# CPU.net
KiCad netlist of a schematic drawn in Altium Designer
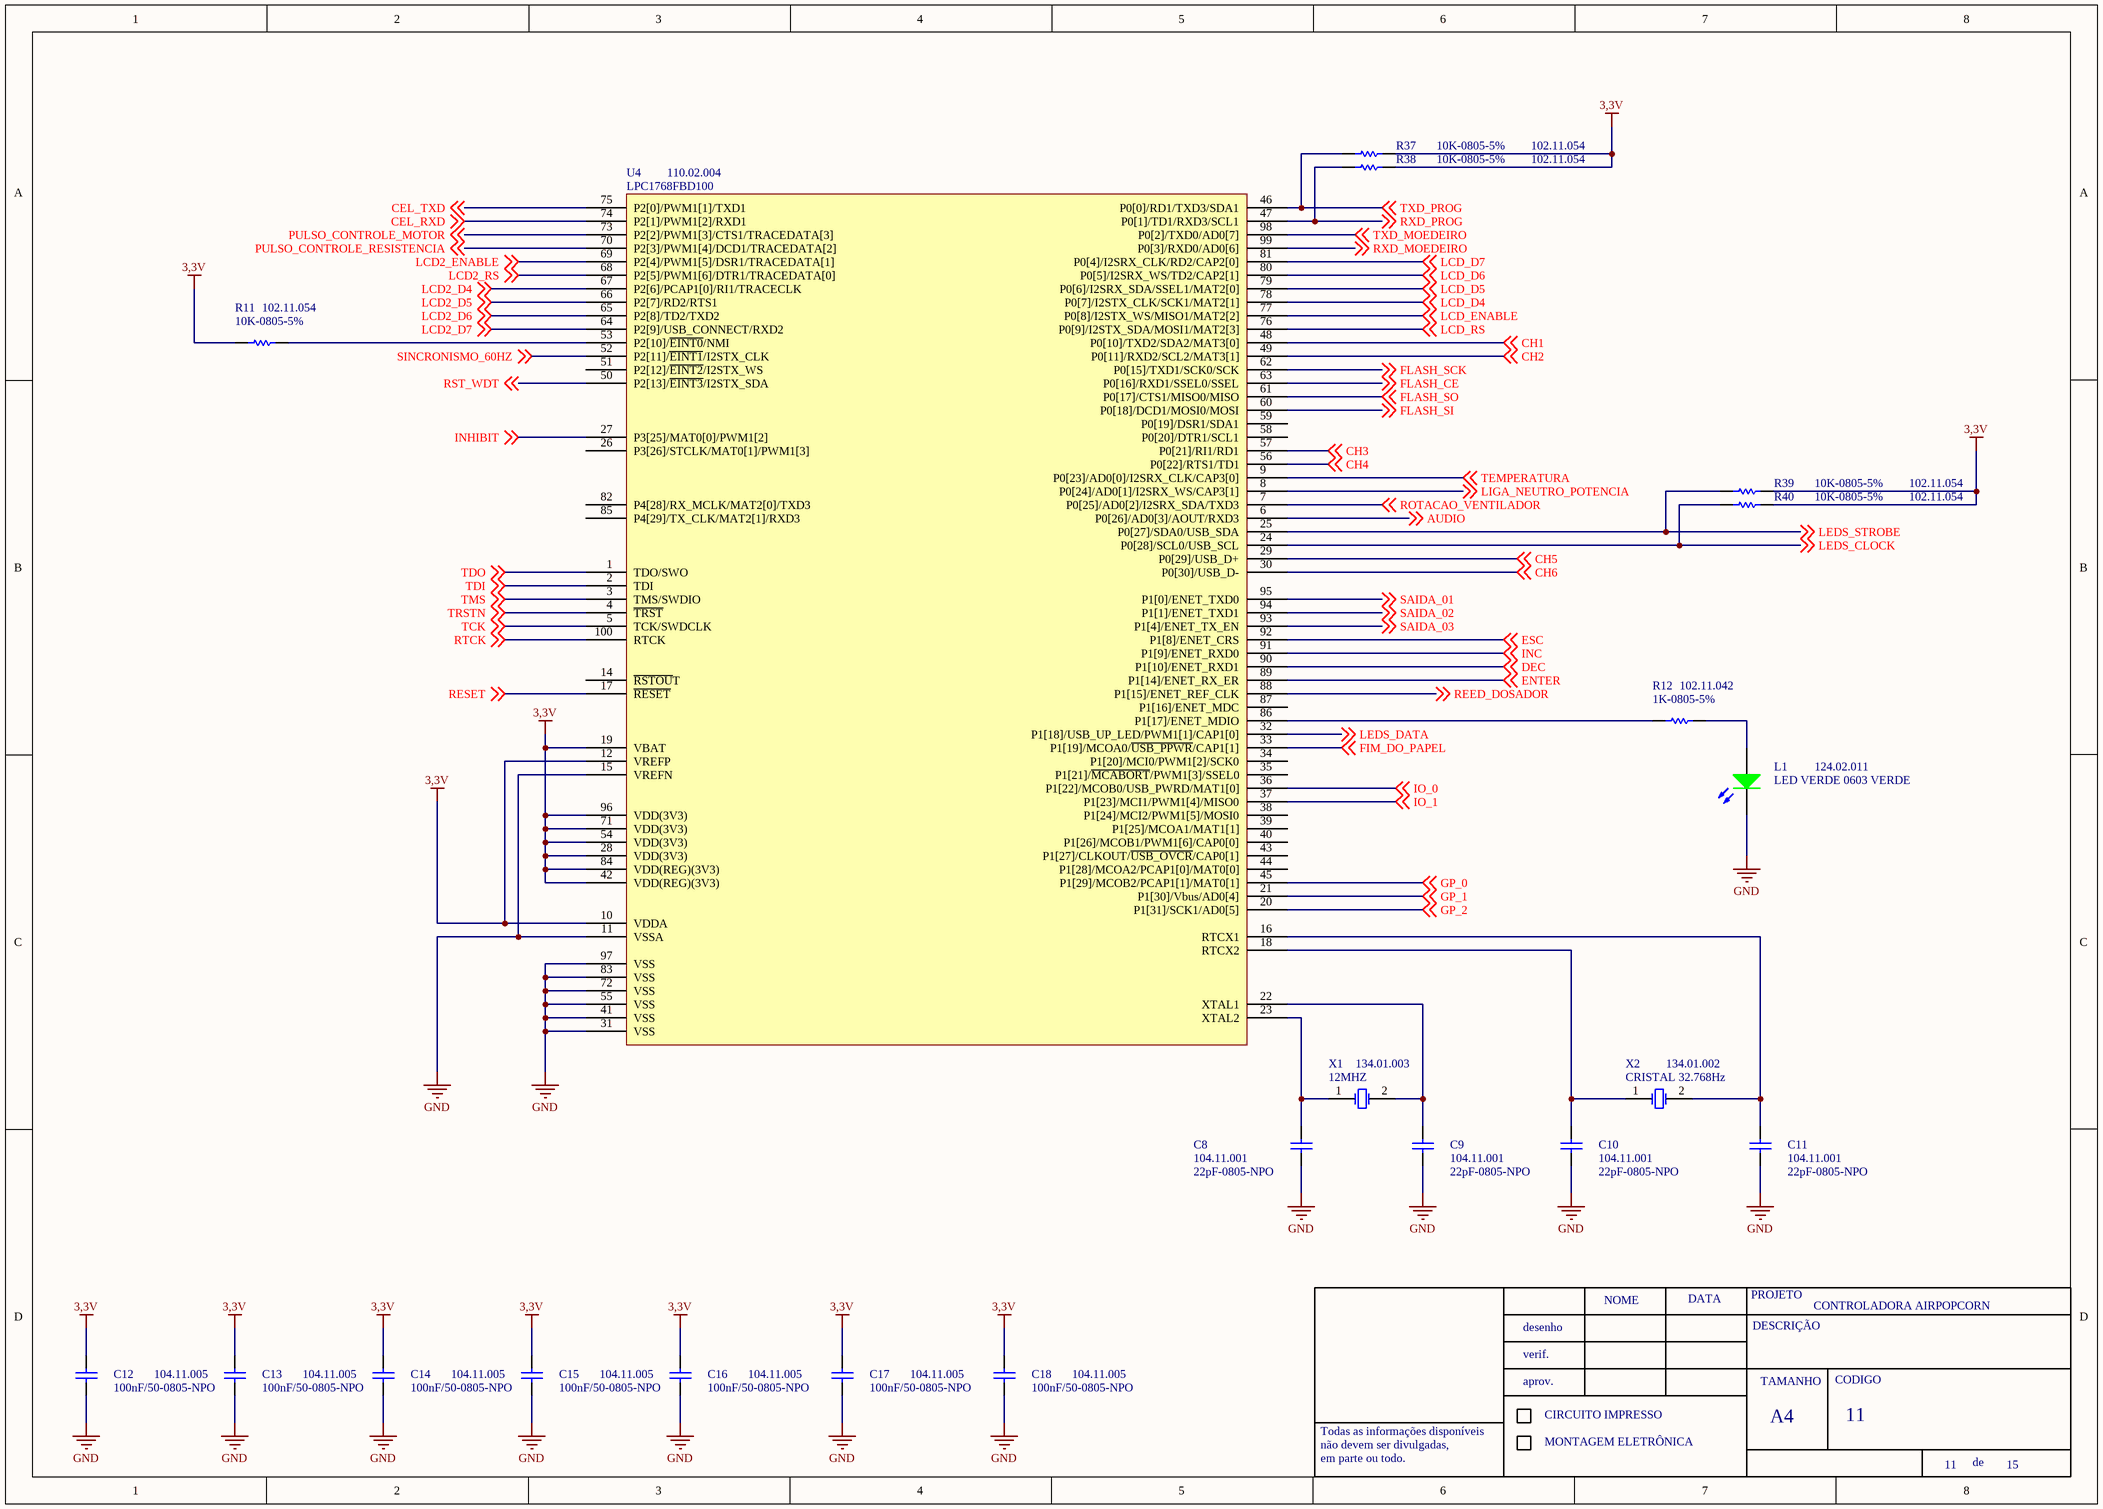
[diagram p0: CPU.SchDoc]

(export (version "E")
  (design (tool "Eeschema 10.0.6"))
  (components
    (comp (ref "C8")
      (value "22pF-0805-NPO")
      (footprint "0805-REVISADO ONDA")
      (fields (field (name "ERP") "104.11.001"))
      (libsource (lib "AquinoLib") (part "22pF-0805-NPO"))
    )
    (comp (ref "C9")
      (value "22pF-0805-NPO")
      (footprint "0805-REVISADO ONDA")
      (fields (field (name "ERP") "104.11.001"))
      (libsource (lib "AquinoLib") (part "22pF-0805-NPO"))
    )
    (comp (ref "C10")
      (value "22pF-0805-NPO")
      (footprint "0805-REVISADO ONDA")
      (fields (field (name "ERP") "104.11.001"))
      (libsource (lib "AquinoLib") (part "22pF-0805-NPO"))
    )
    (comp (ref "C11")
      (value "22pF-0805-NPO")
      (footprint "0805-REVISADO ONDA")
      (fields (field (name "ERP") "104.11.001"))
      (libsource (lib "AquinoLib") (part "22pF-0805-NPO"))
    )
    (comp (ref "C12")
      (value "100nF/50-0805-NPO")
      (footprint "0805-REVISADO ONDA")
      (fields (field (name "ERP") "104.11.005"))
      (libsource (lib "AquinoLib") (part "100nF/50-0805-NPO"))
    )
    (comp (ref "C13")
      (value "100nF/50-0805-NPO")
      (footprint "0805-REVISADO ONDA")
      (fields (field (name "ERP") "104.11.005"))
      (libsource (lib "AquinoLib") (part "100nF/50-0805-NPO"))
    )
    (comp (ref "C14")
      (value "100nF/50-0805-NPO")
      (footprint "0805-REVISADO ONDA")
      (fields (field (name "ERP") "104.11.005"))
      (libsource (lib "AquinoLib") (part "100nF/50-0805-NPO"))
    )
    (comp (ref "C15")
      (value "100nF/50-0805-NPO")
      (footprint "0805-REVISADO ONDA")
      (fields (field (name "ERP") "104.11.005"))
      (libsource (lib "AquinoLib") (part "100nF/50-0805-NPO"))
    )
    (comp (ref "C16")
      (value "100nF/50-0805-NPO")
      (footprint "0805-REVISADO ONDA")
      (fields (field (name "ERP") "104.11.005"))
      (libsource (lib "AquinoLib") (part "100nF/50-0805-NPO"))
    )
    (comp (ref "C17")
      (value "100nF/50-0805-NPO")
      (footprint "0805-REVISADO ONDA")
      (fields (field (name "ERP") "104.11.005"))
      (libsource (lib "AquinoLib") (part "100nF/50-0805-NPO"))
    )
    (comp (ref "C18")
      (value "100nF/50-0805-NPO")
      (footprint "0805-REVISADO ONDA")
      (fields (field (name "ERP") "104.11.005"))
      (libsource (lib "AquinoLib") (part "100nF/50-0805-NPO"))
    )
    (comp (ref "L1")
      (value "LED VERDE 0603 VERDE")
      (footprint "LED 0805 - REVISADO ONDA")
      (fields (field (name "ERP") "124.02.011"))
      (libsource (lib "AquinoLib") (part "LED VERDE 0603 SMD"))
    )
    (comp (ref "R11")
      (value "10K-0805-5%")
      (footprint "0805-REVISADO ONDA")
      (fields (field (name "ERP") "102.11.054"))
      (libsource (lib "AquinoLib") (part "10K-0805-5%"))
    )
    (comp (ref "R12")
      (value "1K-0805-5%")
      (footprint "0805-REVISADO ONDA")
      (fields (field (name "ERP") "102.11.042"))
      (libsource (lib "AquinoLib") (part "1K-0805-5%"))
    )
    (comp (ref "R37")
      (value "10K-0805-5%")
      (footprint "0805-REVISADO ONDA")
      (fields (field (name "ERP") "102.11.054"))
      (libsource (lib "AquinoLib") (part "10K-0805-5%"))
    )
    (comp (ref "R38")
      (value "10K-0805-5%")
      (footprint "0805-REVISADO ONDA")
      (fields (field (name "ERP") "102.11.054"))
      (libsource (lib "AquinoLib") (part "10K-0805-5%"))
    )
    (comp (ref "R39")
      (value "10K-0805-5%")
      (footprint "0805-REVISADO ONDA")
      (fields (field (name "ERP") "102.11.054"))
      (libsource (lib "AquinoLib") (part "10K-0805-5%"))
    )
    (comp (ref "R40")
      (value "10K-0805-5%")
      (footprint "0805-REVISADO ONDA")
      (fields (field (name "ERP") "102.11.054"))
      (libsource (lib "AquinoLib") (part "10K-0805-5%"))
    )
    (comp (ref "U4")
      (value "LPC1768FBD100")
      (footprint "LQFP-100 pasta")
      (fields (field (name "ERP") "110.02.004"))
      (libsource (lib "ChaveDigital3") (part "LPC1768FDB100"))
    )
    (comp (ref "X1")
      (value "12MHZ")
      (footprint "CRISTAL HC49S")
      (fields (field (name "ERP") "134.01.003"))
      (libsource (lib "AquinoLib") (part "CRISTAL 12MHZ"))
    )
    (comp (ref "X2")
      (value "CRISTAL 32.768Hz")
      (footprint "CRISTAL TH3")
      (fields (field (name "ERP") "134.01.002"))
      (libsource (lib "AquinoLib") (part "CRISTAL 32.768 Hz"))
    )
  )
  (nets
    (net (code "1") (name "3,3V") (class "Default")
      (node (ref "C12") (pin "2") (pinfunction "2_2") (pintype "passive"))
      (node (ref "C13") (pin "2") (pinfunction "2_2") (pintype "passive"))
      (node (ref "C14") (pin "2") (pinfunction "2_2") (pintype "passive"))
      (node (ref "C15") (pin "2") (pinfunction "2_2") (pintype "passive"))
      (node (ref "C16") (pin "2") (pinfunction "2_2") (pintype "passive"))
      (node (ref "C17") (pin "2") (pinfunction "2_2") (pintype "passive"))
      (node (ref "C18") (pin "2") (pinfunction "2_2") (pintype "passive"))
      (node (ref "R11") (pin "1") (pinfunction "1_1") (pintype "passive"))
      (node (ref "R37") (pin "2") (pinfunction "2_2") (pintype "passive"))
      (node (ref "R38") (pin "2") (pinfunction "2_2") (pintype "passive"))
      (node (ref "R39") (pin "2") (pinfunction "2_2") (pintype "passive"))
      (node (ref "R40") (pin "2") (pinfunction "2_2") (pintype "passive"))
      (node (ref "U4") (pin "10") (pinfunction "VDDA_10") (pintype "passive"))
      (node (ref "U4") (pin "12") (pinfunction "VREFP_12") (pintype "passive"))
      (node (ref "U4") (pin "19") (pinfunction "VBAT_19") (pintype "passive"))
      (node (ref "U4") (pin "28") (pinfunction "VDD(3V3)_28") (pintype "passive"))
      (node (ref "U4") (pin "42") (pinfunction "VDD(REG)(3V3)_42") (pintype "passive"))
      (node (ref "U4") (pin "54") (pinfunction "VDD(3V3)_54") (pintype "passive"))
      (node (ref "U4") (pin "71") (pinfunction "VDD(3V3)_71") (pintype "passive"))
      (node (ref "U4") (pin "84") (pinfunction "VDD(REG)(3V3)_84") (pintype "passive"))
      (node (ref "U4") (pin "96") (pinfunction "VDD(3V3)_96") (pintype "passive"))
    )
    (net (code "2") (name "AUDIO") (class "Default")
      (node (ref "U4") (pin "6") (pinfunction "P0[26]/AD0[3]/AOUT/RXD3_6") (pintype "passive"))
    )
    (net (code "3") (name "CEL_RXD") (class "Default")
      (node (ref "U4") (pin "74") (pinfunction "P2[1]/PWM1[2]/RXD1_74") (pintype "passive"))
    )
    (net (code "4") (name "CEL_TXD") (class "Default")
      (node (ref "U4") (pin "75") (pinfunction "P2[0]/PWM1[1]/TXD1_75") (pintype "passive"))
    )
    (net (code "5") (name "CH1") (class "Default")
      (node (ref "U4") (pin "48") (pinfunction "P0[10]/TXD2/SDA2/MAT3[0]_48") (pintype "passive"))
    )
    (net (code "6") (name "CH2") (class "Default")
      (node (ref "U4") (pin "49") (pinfunction "P0[11]/RXD2/SCL2/MAT3[1]_49") (pintype "passive"))
    )
    (net (code "7") (name "CH3") (class "Default")
      (node (ref "U4") (pin "57") (pinfunction "P0[21]/RI1/RD1_57") (pintype "passive"))
    )
    (net (code "8") (name "CH4") (class "Default")
      (node (ref "U4") (pin "56") (pinfunction "P0[22]/RTS1/TD1_56") (pintype "passive"))
    )
    (net (code "9") (name "CH5") (class "Default")
      (node (ref "U4") (pin "29") (pinfunction "P0[29]/USB_D+_29") (pintype "passive"))
    )
    (net (code "10") (name "CH6") (class "Default")
      (node (ref "U4") (pin "30") (pinfunction "P0[30]/USB_D-_30") (pintype "passive"))
    )
    (net (code "11") (name "DEC") (class "Default")
      (node (ref "U4") (pin "90") (pinfunction "P1[10]/ENET_RXD1_90") (pintype "passive"))
    )
    (net (code "12") (name "ENTER") (class "Default")
      (node (ref "U4") (pin "89") (pinfunction "P1[14]/ENET_RX_ER_89") (pintype "passive"))
    )
    (net (code "13") (name "ESC") (class "Default")
      (node (ref "U4") (pin "92") (pinfunction "P1[8]/ENET_CRS_92") (pintype "passive"))
    )
    (net (code "14") (name "FIM_DO_PAPEL") (class "Default")
      (node (ref "U4") (pin "33") (pinfunction "P1[19]/MCOA0/~{USB_PPWR}/CAP1[1]_33") (pintype "passive"))
    )
    (net (code "15") (name "FLASH_CE") (class "Default")
      (node (ref "U4") (pin "63") (pinfunction "P0[16]/RXD1/SSEL0/SSEL_63") (pintype "passive"))
    )
    (net (code "16") (name "FLASH_SCK") (class "Default")
      (node (ref "U4") (pin "62") (pinfunction "P0[15]/TXD1/SCK0/SCK_62") (pintype "passive"))
    )
    (net (code "17") (name "FLASH_SI") (class "Default")
      (node (ref "U4") (pin "60") (pinfunction "P0[18]/DCD1/MOSI0/MOSI_60") (pintype "passive"))
    )
    (net (code "18") (name "FLASH_SO") (class "Default")
      (node (ref "U4") (pin "61") (pinfunction "P0[17]/CTS1/MISO0/MISO_61") (pintype "passive"))
    )
    (net (code "19") (name "GND") (class "Default")
      (node (ref "C10") (pin "1") (pinfunction "1_1") (pintype "passive"))
      (node (ref "C11") (pin "1") (pinfunction "1_1") (pintype "passive"))
      (node (ref "C12") (pin "1") (pinfunction "1_1") (pintype "passive"))
      (node (ref "C13") (pin "1") (pinfunction "1_1") (pintype "passive"))
      (node (ref "C14") (pin "1") (pinfunction "1_1") (pintype "passive"))
      (node (ref "C15") (pin "1") (pinfunction "1_1") (pintype "passive"))
      (node (ref "C16") (pin "1") (pinfunction "1_1") (pintype "passive"))
      (node (ref "C17") (pin "1") (pinfunction "1_1") (pintype "passive"))
      (node (ref "C18") (pin "1") (pinfunction "1_1") (pintype "passive"))
      (node (ref "C8") (pin "1") (pinfunction "1_1") (pintype "passive"))
      (node (ref "C9") (pin "1") (pinfunction "1_1") (pintype "passive"))
      (node (ref "L1") (pin "2") (pinfunction "K_2") (pintype "passive"))
      (node (ref "U4") (pin "11") (pinfunction "VSSA_11") (pintype "passive"))
      (node (ref "U4") (pin "15") (pinfunction "VREFN_15") (pintype "passive"))
      (node (ref "U4") (pin "31") (pinfunction "VSS_31") (pintype "passive"))
      (node (ref "U4") (pin "41") (pinfunction "VSS_41") (pintype "passive"))
      (node (ref "U4") (pin "55") (pinfunction "VSS_55") (pintype "passive"))
      (node (ref "U4") (pin "72") (pinfunction "VSS_72") (pintype "passive"))
      (node (ref "U4") (pin "83") (pinfunction "VSS_83") (pintype "passive"))
      (node (ref "U4") (pin "97") (pinfunction "VSS_97") (pintype "passive"))
    )
    (net (code "20") (name "GP_0") (class "Default")
      (node (ref "U4") (pin "45") (pinfunction "P1[29]/MCOB2/PCAP1[1]/MAT0[1]_45") (pintype "passive"))
    )
    (net (code "21") (name "GP_1") (class "Default")
      (node (ref "U4") (pin "21") (pinfunction "P1[30]/Vbus/AD0[4]_21") (pintype "passive"))
    )
    (net (code "22") (name "GP_2") (class "Default")
      (node (ref "U4") (pin "20") (pinfunction "P1[31]/SCK1/AD0[5]_20") (pintype "passive"))
    )
    (net (code "23") (name "INC") (class "Default")
      (node (ref "U4") (pin "91") (pinfunction "P1[9]/ENET_RXD0_91") (pintype "passive"))
    )
    (net (code "24") (name "INHIBIT") (class "Default")
      (node (ref "U4") (pin "27") (pinfunction "P3[25]/MAT0[0]/PWM1[2]_27") (pintype "passive"))
    )
    (net (code "25") (name "IO_0") (class "Default")
      (node (ref "U4") (pin "36") (pinfunction "P1[22]/MCOB0/USB_PWRD/MAT1[0]_36") (pintype "passive"))
    )
    (net (code "26") (name "IO_1") (class "Default")
      (node (ref "U4") (pin "37") (pinfunction "P1[23]/MCI1/PWM1[4]/MISO0_37") (pintype "passive"))
    )
    (net (code "27") (name "LCD2_D4") (class "Default")
      (node (ref "U4") (pin "67") (pinfunction "P2[6]/PCAP1[0]/RI1/TRACECLK_67") (pintype "passive"))
    )
    (net (code "28") (name "LCD2_D5") (class "Default")
      (node (ref "U4") (pin "66") (pinfunction "P2[7]/RD2/RTS1_66") (pintype "passive"))
    )
    (net (code "29") (name "LCD2_D6") (class "Default")
      (node (ref "U4") (pin "65") (pinfunction "P2[8]/TD2/TXD2_65") (pintype "passive"))
    )
    (net (code "30") (name "LCD2_D7") (class "Default")
      (node (ref "U4") (pin "64") (pinfunction "P2[9]/USB_CONNECT/RXD2_64") (pintype "passive"))
    )
    (net (code "31") (name "LCD2_ENABLE") (class "Default")
      (node (ref "U4") (pin "69") (pinfunction "P2[4]/PWM1[5]/DSR1/TRACEDATA[1]_69") (pintype "passive"))
    )
    (net (code "32") (name "LCD2_RS") (class "Default")
      (node (ref "U4") (pin "68") (pinfunction "P2[5]/PWM1[6]/DTR1/TRACEDATA[0]_68") (pintype "passive"))
    )
    (net (code "33") (name "LCD_D4") (class "Default")
      (node (ref "U4") (pin "78") (pinfunction "P0[7]/I2STX_CLK/SCK1/MAT2[1]_78") (pintype "passive"))
    )
    (net (code "34") (name "LCD_D5") (class "Default")
      (node (ref "U4") (pin "79") (pinfunction "P0[6]/I2SRX_SDA/SSEL1/MAT2[0]_79") (pintype "passive"))
    )
    (net (code "35") (name "LCD_D6") (class "Default")
      (node (ref "U4") (pin "80") (pinfunction "P0[5]/I2SRX_WS/TD2/CAP2[1]_80") (pintype "passive"))
    )
    (net (code "36") (name "LCD_D7") (class "Default")
      (node (ref "U4") (pin "81") (pinfunction "P0[4]/I2SRX_CLK/RD2/CAP2[0]_81") (pintype "passive"))
    )
    (net (code "37") (name "LCD_ENABLE") (class "Default")
      (node (ref "U4") (pin "77") (pinfunction "P0[8]/I2STX_WS/MISO1/MAT2[2]_77") (pintype "passive"))
    )
    (net (code "38") (name "LCD_RS") (class "Default")
      (node (ref "U4") (pin "76") (pinfunction "P0[9]/I2STX_SDA/MOSI1/MAT2[3]_76") (pintype "passive"))
    )
    (net (code "39") (name "LEDS_CLOCK") (class "Default")
      (node (ref "R40") (pin "1") (pinfunction "1_1") (pintype "passive"))
      (node (ref "U4") (pin "24") (pinfunction "P0[28]/SCL0/USB_SCL_24") (pintype "passive"))
    )
    (net (code "40") (name "LEDS_DATA") (class "Default")
      (node (ref "U4") (pin "32") (pinfunction "P1[18]/USB_UP_LED/PWM1[1]/CAP1[0]_32") (pintype "passive"))
    )
    (net (code "41") (name "LEDS_STROBE") (class "Default")
      (node (ref "R39") (pin "1") (pinfunction "1_1") (pintype "passive"))
      (node (ref "U4") (pin "25") (pinfunction "P0[27]/SDA0/USB_SDA_25") (pintype "passive"))
    )
    (net (code "42") (name "LIGA_NEUTRO_POTENCIA") (class "Default")
      (node (ref "U4") (pin "8") (pinfunction "P0[24]/AD0[1]/I2SRX_WS/CAP3[1]_8") (pintype "passive"))
    )
    (net (code "43") (name "Net-(L1-A)") (class "Default")
      (node (ref "L1") (pin "1") (pinfunction "A_1") (pintype "passive"))
      (node (ref "R12") (pin "2") (pinfunction "2_2") (pintype "passive"))
    )
    (net (code "44") (name "Net-(U4-P1[17]{slash}ENET_MDIO)") (class "Default")
      (node (ref "R12") (pin "1") (pinfunction "1_1") (pintype "passive"))
      (node (ref "U4") (pin "86") (pinfunction "P1[17]/ENET_MDIO_86") (pintype "passive"))
    )
    (net (code "45") (name "Net-(U4-P2[10]{slash}~{EINT0}{slash}NMI)") (class "Default")
      (node (ref "R11") (pin "2") (pinfunction "2_2") (pintype "passive"))
      (node (ref "U4") (pin "53") (pinfunction "P2[10]/~{EINT0}/NMI_53") (pintype "passive"))
    )
    (net (code "46") (name "Net-(U4-RTCX1)") (class "Default")
      (node (ref "C11") (pin "2") (pinfunction "2_2") (pintype "passive"))
      (node (ref "U4") (pin "16") (pinfunction "RTCX1_16") (pintype "passive"))
      (node (ref "X2") (pin "2") (pinfunction "OSC2_2") (pintype "passive"))
    )
    (net (code "47") (name "Net-(U4-RTCX2)") (class "Default")
      (node (ref "C10") (pin "2") (pinfunction "2_2") (pintype "passive"))
      (node (ref "U4") (pin "18") (pinfunction "RTCX2_18") (pintype "passive"))
      (node (ref "X2") (pin "1") (pinfunction "OSC1_1") (pintype "passive"))
    )
    (net (code "48") (name "Net-(U4-XTAL1)") (class "Default")
      (node (ref "C9") (pin "2") (pinfunction "2_2") (pintype "passive"))
      (node (ref "U4") (pin "22") (pinfunction "XTAL1_22") (pintype "passive"))
      (node (ref "X1") (pin "2") (pinfunction "OSC2_2") (pintype "passive"))
    )
    (net (code "49") (name "Net-(U4-XTAL2)") (class "Default")
      (node (ref "C8") (pin "2") (pinfunction "2_2") (pintype "passive"))
      (node (ref "U4") (pin "23") (pinfunction "XTAL2_23") (pintype "passive"))
      (node (ref "X1") (pin "1") (pinfunction "OSC1_1") (pintype "passive"))
    )
    (net (code "50") (name "PULSO_CONTROLE_MOTOR") (class "Default")
      (node (ref "U4") (pin "73") (pinfunction "P2[2]/PWM1[3]/CTS1/TRACEDATA[3]_73") (pintype "passive"))
    )
    (net (code "51") (name "PULSO_CONTROLE_RESISTENCIA") (class "Default")
      (node (ref "U4") (pin "70") (pinfunction "P2[3]/PWM1[4]/DCD1/TRACEDATA[2]_70") (pintype "passive"))
    )
    (net (code "52") (name "REED_DOSADOR") (class "Default")
      (node (ref "U4") (pin "88") (pinfunction "P1[15]/ENET_REF_CLK_88") (pintype "passive"))
    )
    (net (code "53") (name "RESET") (class "Default")
      (node (ref "U4") (pin "17") (pinfunction "~{RESET}_17") (pintype "passive"))
    )
    (net (code "54") (name "ROTACAO_VENTILADOR") (class "Default")
      (node (ref "U4") (pin "7") (pinfunction "P0[25]/AD0[2]/I2SRX_SDA/TXD3_7") (pintype "passive"))
    )
    (net (code "55") (name "RST_WDT") (class "Default")
      (node (ref "U4") (pin "50") (pinfunction "P2[13]/~{EINT3}/I2STX_SDA_50") (pintype "passive"))
    )
    (net (code "56") (name "RTCK") (class "Default")
      (node (ref "U4") (pin "100") (pinfunction "RTCK_100") (pintype "passive"))
    )
    (net (code "57") (name "RXD_MOEDEIRO") (class "Default")
      (node (ref "U4") (pin "99") (pinfunction "P0[3]/RXD0/AD0[6]_99") (pintype "passive"))
    )
    (net (code "58") (name "RXD_PROG") (class "Default")
      (node (ref "R38") (pin "1") (pinfunction "1_1") (pintype "passive"))
      (node (ref "U4") (pin "47") (pinfunction "P0[1]/TD1/RXD3/SCL1_47") (pintype "passive"))
    )
    (net (code "59") (name "SAIDA_01") (class "Default")
      (node (ref "U4") (pin "95") (pinfunction "P1[0]/ENET_TXD0_95") (pintype "passive"))
    )
    (net (code "60") (name "SAIDA_02") (class "Default")
      (node (ref "U4") (pin "94") (pinfunction "P1[1]/ENET_TXD1_94") (pintype "passive"))
    )
    (net (code "61") (name "SAIDA_03") (class "Default")
      (node (ref "U4") (pin "93") (pinfunction "P1[4]/ENET_TX_EN_93") (pintype "passive"))
    )
    (net (code "62") (name "SINCRONISMO_60HZ") (class "Default")
      (node (ref "U4") (pin "52") (pinfunction "P2[11]/~{EINT1}/I2STX_CLK_52") (pintype "passive"))
    )
    (net (code "63") (name "TCK") (class "Default")
      (node (ref "U4") (pin "5") (pinfunction "TCK/SWDCLK_5") (pintype "passive"))
    )
    (net (code "64") (name "TDI") (class "Default")
      (node (ref "U4") (pin "2") (pinfunction "TDI_2") (pintype "passive"))
    )
    (net (code "65") (name "TDO") (class "Default")
      (node (ref "U4") (pin "1") (pinfunction "TDO/SWO_1") (pintype "passive"))
    )
    (net (code "66") (name "TEMPERATURA") (class "Default")
      (node (ref "U4") (pin "9") (pinfunction "P0[23]/AD0[0]/I2SRX_CLK/CAP3[0]_9") (pintype "passive"))
    )
    (net (code "67") (name "TMS") (class "Default")
      (node (ref "U4") (pin "3") (pinfunction "TMS/SWDIO_3") (pintype "passive"))
    )
    (net (code "68") (name "TRSTN") (class "Default")
      (node (ref "U4") (pin "4") (pinfunction "~{TRST}_4") (pintype "passive"))
    )
    (net (code "69") (name "TXD_MOEDEIRO") (class "Default")
      (node (ref "U4") (pin "98") (pinfunction "P0[2]/TXD0/AD0[7]_98") (pintype "passive"))
    )
    (net (code "70") (name "TXD_PROG") (class "Default")
      (node (ref "R37") (pin "1") (pinfunction "1_1") (pintype "passive"))
      (node (ref "U4") (pin "46") (pinfunction "P0[0]/RD1/TXD3/SDA1_46") (pintype "passive"))
    )
    (net (code "71") (name "unconnected-(U4-P0[19]{slash}DSR1{slash}SDA1-Pad59)") (class "Default")
      (node (ref "U4") (pin "59") (pinfunction "P0[19]/DSR1/SDA1_59") (pintype "passive"))
    )
    (net (code "72") (name "unconnected-(U4-P0[20]{slash}DTR1{slash}SCL1-Pad58)") (class "Default")
      (node (ref "U4") (pin "58") (pinfunction "P0[20]/DTR1/SCL1_58") (pintype "passive"))
    )
    (net (code "73") (name "unconnected-(U4-P1[16]{slash}ENET_MDC-Pad87)") (class "Default")
      (node (ref "U4") (pin "87") (pinfunction "P1[16]/ENET_MDC_87") (pintype "passive"))
    )
    (net (code "74") (name "unconnected-(U4-P1[20]{slash}MCI0{slash}PWM1[2]{slash}SCK0-Pad34)") (class "Default")
      (node (ref "U4") (pin "34") (pinfunction "P1[20]/MCI0/PWM1[2]/SCK0_34") (pintype "passive"))
    )
    (net (code "75") (name "unconnected-(U4-P1[21]{slash}~{MCABORT}{slash}PWM1[3]{slash}SSEL0-Pad35)") (class "Default")
      (node (ref "U4") (pin "35") (pinfunction "P1[21]/~{MCABORT}/PWM1[3]/SSEL0_35") (pintype "passive"))
    )
    (net (code "76") (name "unconnected-(U4-P1[24]{slash}MCI2{slash}PWM1[5]{slash}MOSI0-Pad38)") (class "Default")
      (node (ref "U4") (pin "38") (pinfunction "P1[24]/MCI2/PWM1[5]/MOSI0_38") (pintype "passive"))
    )
    (net (code "77") (name "unconnected-(U4-P1[25]{slash}MCOA1{slash}MAT1[1]-Pad39)") (class "Default")
      (node (ref "U4") (pin "39") (pinfunction "P1[25]/MCOA1/MAT1[1]_39") (pintype "passive"))
    )
    (net (code "78") (name "unconnected-(U4-P1[26]{slash}MCOB1{slash}PWM1[6]{slash}CAP0[0]-Pad40)") (class "Default")
      (node (ref "U4") (pin "40") (pinfunction "P1[26]/MCOB1/PWM1[6]/CAP0[0]_40") (pintype "passive"))
    )
    (net (code "79") (name "unconnected-(U4-P1[27]{slash}CLKOUT{slash}~{USB_OVCR}{slash}CAP0[1]-Pad43)") (class "Default")
      (node (ref "U4") (pin "43") (pinfunction "P1[27]/CLKOUT/~{USB_OVCR}/CAP0[1]_43") (pintype "passive"))
    )
    (net (code "80") (name "unconnected-(U4-P1[28]{slash}MCOA2{slash}PCAP1[0]{slash}MAT0[0]-Pad44)") (class "Default")
      (node (ref "U4") (pin "44") (pinfunction "P1[28]/MCOA2/PCAP1[0]/MAT0[0]_44") (pintype "passive"))
    )
    (net (code "81") (name "unconnected-(U4-P2[12]{slash}~{EINT2}{slash}I2STX_WS-Pad51)") (class "Default")
      (node (ref "U4") (pin "51") (pinfunction "P2[12]/~{EINT2}/I2STX_WS_51") (pintype "passive"))
    )
    (net (code "82") (name "unconnected-(U4-P3[26]{slash}STCLK{slash}MAT0[1]{slash}PWM1[3]-Pad26)") (class "Default")
      (node (ref "U4") (pin "26") (pinfunction "P3[26]/STCLK/MAT0[1]/PWM1[3]_26") (pintype "passive"))
    )
    (net (code "83") (name "unconnected-(U4-P4[28]{slash}RX_MCLK{slash}MAT2[0]{slash}TXD3-Pad82)") (class "Default")
      (node (ref "U4") (pin "82") (pinfunction "P4[28]/RX_MCLK/MAT2[0]/TXD3_82") (pintype "passive"))
    )
    (net (code "84") (name "unconnected-(U4-P4[29]{slash}TX_CLK{slash}MAT2[1]{slash}RXD3-Pad85)") (class "Default")
      (node (ref "U4") (pin "85") (pinfunction "P4[29]/TX_CLK/MAT2[1]/RXD3_85") (pintype "passive"))
    )
    (net (code "85") (name "unconnected-(U4-~{RSTOU}T-Pad14)") (class "Default")
      (node (ref "U4") (pin "14") (pinfunction "~{RSTOU}T_14") (pintype "passive"))
    )
  )
)
